# Power.net
KiCad netlist of a schematic drawn in Altium Designer
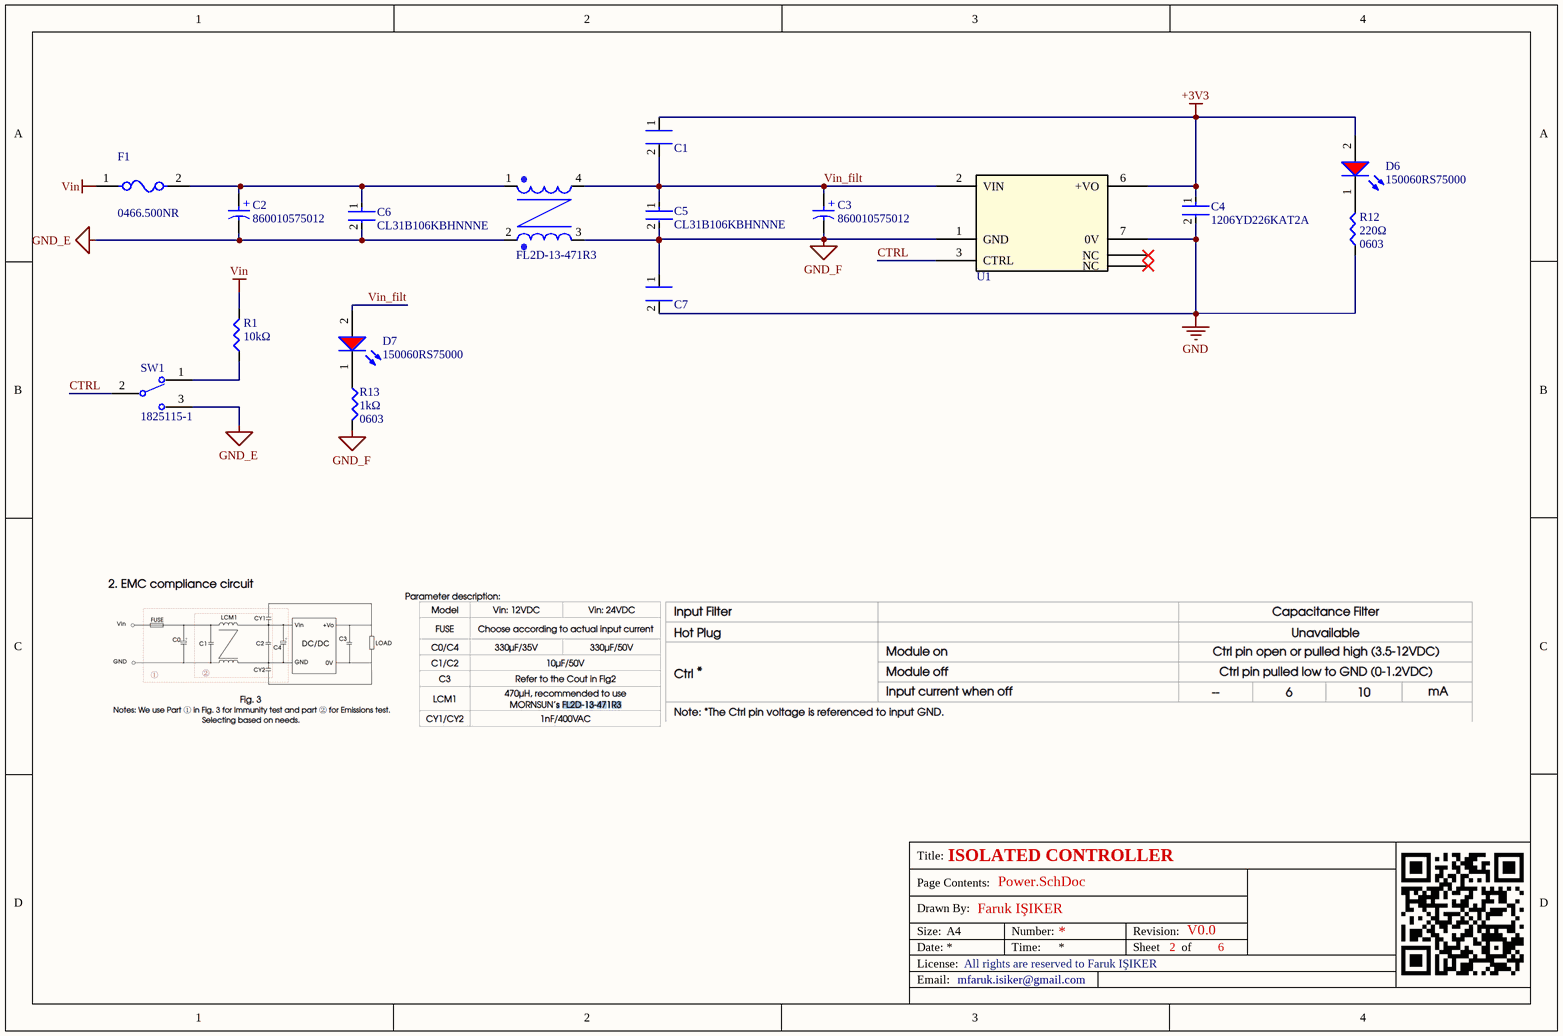
[diagram p0: Power.SchDoc]

(export (version "E")
  (design (tool "Eeschema 10.0.6"))
  (components
    (comp (ref "C1")
      (value "1nf 400V AC 7.5mm Lead")
      (footprint "PCBComponent_1")
      (description "Suppression Cap, 1000Pf, Class X1/ Y2 Rohs Compliant: Yes ¦Kemet C717U102MYVDBA7317")
      (fields
        (field (name "MANUFACTURER") "KEMET")
        (field (name "MANUFACTURER PART NUMBER") "C717U102MYVDBA7317")
      )
      (libsource (lib "Schlib1") (part "C717U102MYVDBA7317"))
    )
    (comp (ref "C2")
      (value "860010575012")
      (footprint "WCAP-ATG8_D10H12.5")
      (description "860010575012 WCAP-ATG8 Aluminum Electrolytic Capacitors")
      (fields (field (name "TOLERANCE") "20%"))
      (libsource (lib "Altium Content Vault") (part "Capacitor_Polarized"))
    )
    (comp (ref "C3")
      (value "860010575012")
      (footprint "WCAP-ATG8_D10H12.5")
      (description "860010575012 WCAP-ATG8 Aluminum Electrolytic Capacitors")
      (fields (field (name "TOLERANCE") "20%"))
      (libsource (lib "Altium Content Vault") (part "Capacitor_Polarized"))
    )
    (comp (ref "C4")
      (value "1206YD226KAT2A")
      (footprint "FP-1206-L_3_2_0_2-W_1_6_0-IPC_A")
      (description "General Purpose Ceramic Capacitor, 1206, 22uF, 10%, X5R, 15%, 16V")
      (fields (field (name "TOLERANCE") "10%"))
      (libsource (lib "Altium Content Vault") (part "02cd4be3c70576c341d710602a673aa"))
    )
    (comp (ref "C5")
      (value "CL31B106KBHNNNE")
      (footprint "FP-CL31B106KBHNNNE-IPC_A")
      (description "CAP CER 10UF 50V X7R 1206")
      (fields (field (name "MANUFACTURER") "Samsung") (field (name "TOLERANCE") "10%"))
      (libsource (lib "Altium Content Vault") (part "b4654b650e69147ec39a6b967a45e02"))
    )
    (comp (ref "C6")
      (value "CL31B106KBHNNNE")
      (footprint "FP-CL31B106KBHNNNE-IPC_A")
      (description "CAP CER 10UF 50V X7R 1206")
      (fields (field (name "MANUFACTURER") "Samsung") (field (name "TOLERANCE") "10%"))
      (libsource (lib "Altium Content Vault") (part "b4654b650e69147ec39a6b967a45e02"))
    )
    (comp (ref "C7")
      (value "1nf 400V AC 7.5mm Lead")
      (footprint "PCBComponent_1")
      (description "Suppression Cap, 1000Pf, Class X1/ Y2 Rohs Compliant: Yes ¦Kemet C717U102MYVDBA7317")
      (fields
        (field (name "MANUFACTURER") "KEMET")
        (field (name "MANUFACTURER PART NUMBER") "C717U102MYVDBA7317")
      )
      (libsource (lib "Schlib1") (part "C717U102MYVDBA7317"))
    )
    (comp (ref "D6")
      (value "150060RS75000")
      (footprint "WL-SMCW_0603_150060xx75000")
      (libsource (lib "Altium Content Vault") (part "LED_Red_2A-1K"))
    )
    (comp (ref "D7")
      (value "150060RS75000")
      (footprint "WL-SMCW_0603_150060xx75000")
      (libsource (lib "Altium Content Vault") (part "LED_Red_2A-1K"))
    )
    (comp (ref "F1")
      (value "0466.500NR")
      (footprint "FP-0466-MFG")
      (description "FUSE BOARD MOUNT 500MA 63VAC/VDC")
      (fields
        (field (name "OCTOPART") "https://octopart.com/0466.500nr-littelfuse-566004")
        (field (name "MANUFACTURER") "Littelfuse Inc")
      )
      (libsource (lib "Altium Content Vault") (part "5bcf9b9f640e542cf0359d10258e979"))
    )
    (comp (ref "FL2D-13-471R3")
      (value "EMC Filte")
      (footprint "FL2D-13-471R3")
      (libsource (lib "FL2D-13-471R3") (part "FL2D-13-471R3"))
    )
    (comp (ref "R1")
      (value "10kΩ")
      (footprint "0603-smd")
      (fields (field (name "POWER") "W") (field (name "Comment") "0603_10K"))
      (libsource (lib "generic") (part "0603_10K"))
    )
    (comp (ref "R12")
      (value "220Ω")
      (footprint "0603-smd")
      (fields (field (name "POWER") "W") (field (name "PACKAGE") "0603") (field (name "Comment") "0603_220R"))
      (libsource (lib "generic") (part "0603_220R"))
    )
    (comp (ref "R13")
      (value "1kΩ")
      (footprint "0603-smd")
      (fields (field (name "POWER") "W") (field (name "PACKAGE") "0603") (field (name "Comment") "0603_1K"))
      (libsource (lib "generic") (part "0603_1K"))
    )
    (comp (ref "SW1")
      (value "1825115-1")
      (footprint "FP-1825115-1-MFG")
      (description "SWITCH SLIDE SPDT 250MA 125V")
      (fields
        (field (name "MANUFACTURER") "TE Connectivity")
        (field (name "OCTOPART") "https://octopart.com/sls121pc04-te+connectivity-39426454")
      )
      (libsource (lib "Altium Content Vault") (part "ec4e4964ed0d2d669af15d5af94fda9"))
    )
    (comp (ref "U1")
      (value "DC DC CONVERTER 3.3V 6W")
      (footprint "VRB_S-6WR3_MNS")
      (description "Isolated Module DC DC Converter 1 Output 3.3V 1.35A 9V - 18V Input")
      (libsource (lib "VRB1203S-6WR3") (part "VRB1203S-6WR3"))
    )
  )
  (nets
    (net (code "1") (name "+3V3") (class "Default")
      (node (ref "C1") (pin "1") (pinfunction "1_1") (pintype "passive"))
      (node (ref "C4") (pin "1") (pinfunction "1_1") (pintype "passive"))
      (node (ref "D6") (pin "2") (pinfunction "A_2") (pintype "passive"))
      (node (ref "U1") (pin "6") (pinfunction "+VO_6") (pintype "power_in"))
    )
    (net (code "2") (name "/CTRL") (class "Default")
      (node (ref "SW1") (pin "2") (pinfunction "2_2") (pintype "passive"))
      (node (ref "U1") (pin "3") (pinfunction "CTRL_3") (pintype "passive"))
    )
    (net (code "3") (name "/Vin_filt") (class "Default")
      (node (ref "C1") (pin "2") (pinfunction "2_2") (pintype "passive"))
      (node (ref "C3") (pin "1") (pinfunction "P_1") (pintype "passive"))
      (node (ref "C5") (pin "1") (pinfunction "1_1") (pintype "passive"))
      (node (ref "D7") (pin "2") (pinfunction "A_2") (pintype "passive"))
      (node (ref "FL2D-13-471R3") (pin "4") (pinfunction "4_4") (pintype "passive"))
      (node (ref "U1") (pin "2") (pinfunction "VIN_2") (pintype "passive"))
    )
    (net (code "4") (name "GND") (class "Default")
      (node (ref "C4") (pin "2") (pinfunction "2_2") (pintype "passive"))
      (node (ref "C7") (pin "2") (pinfunction "2_2") (pintype "passive"))
      (node (ref "R12") (pin "1") (pinfunction "1_1") (pintype "passive"))
      (node (ref "U1") (pin "7") (pinfunction "0V_7") (pintype "passive"))
    )
    (net (code "5") (name "GND_E") (class "Default")
      (node (ref "C2") (pin "2") (pinfunction "N_2") (pintype "passive"))
      (node (ref "C6") (pin "2") (pinfunction "2_2") (pintype "passive"))
      (node (ref "FL2D-13-471R3") (pin "2") (pinfunction "2_2") (pintype "passive"))
      (node (ref "SW1") (pin "3") (pinfunction "3_3") (pintype "passive"))
    )
    (net (code "6") (name "GND_F") (class "Default")
      (node (ref "C3") (pin "2") (pinfunction "N_2") (pintype "passive"))
      (node (ref "C5") (pin "2") (pinfunction "2_2") (pintype "passive"))
      (node (ref "C7") (pin "1") (pinfunction "1_1") (pintype "passive"))
      (node (ref "FL2D-13-471R3") (pin "3") (pinfunction "3_3") (pintype "passive"))
      (node (ref "R13") (pin "2") (pinfunction "2_2") (pintype "passive"))
      (node (ref "U1") (pin "1") (pinfunction "GND_1") (pintype "power_in"))
    )
    (net (code "7") (name "Net-(C2-P)") (class "Default")
      (node (ref "C2") (pin "1") (pinfunction "P_1") (pintype "passive"))
      (node (ref "C6") (pin "1") (pinfunction "1_1") (pintype "passive"))
      (node (ref "F1") (pin "2") (pinfunction "2_2") (pintype "passive"))
      (node (ref "FL2D-13-471R3") (pin "1") (pinfunction "1_1") (pintype "passive"))
    )
    (net (code "8") (name "Net-(D6-K)") (class "Default")
      (node (ref "D6") (pin "1") (pinfunction "K_1") (pintype "passive"))
      (node (ref "R12") (pin "2") (pinfunction "2_2") (pintype "passive"))
    )
    (net (code "9") (name "Net-(D7-K)") (class "Default")
      (node (ref "D7") (pin "1") (pinfunction "K_1") (pintype "passive"))
      (node (ref "R13") (pin "1") (pinfunction "1_1") (pintype "passive"))
    )
    (net (code "10") (name "Net-(R1-Pad1)") (class "Default")
      (node (ref "R1") (pin "1") (pinfunction "1_1") (pintype "passive"))
      (node (ref "SW1") (pin "1") (pinfunction "1_1") (pintype "passive"))
    )
    (net (code "11") (name "Vin") (class "Default")
      (node (ref "F1") (pin "1") (pinfunction "1_1") (pintype "passive"))
      (node (ref "R1") (pin "2") (pinfunction "2_2") (pintype "passive"))
    )
    (net (code "12") (name "unconnected-(U1-NC-Pad5)") (class "Default")
      (node (ref "U1") (pin "5") (pinfunction "NC_5") (pintype "passive+no_connect"))
    )
    (net (code "13") (name "unconnected-(U1-NC-Pad8)") (class "Default")
      (node (ref "U1") (pin "8") (pinfunction "NC_8") (pintype "passive+no_connect"))
    )
  )
)
